# armBandShield.net
KiCad netlist of a schematic drawn in EAGLE
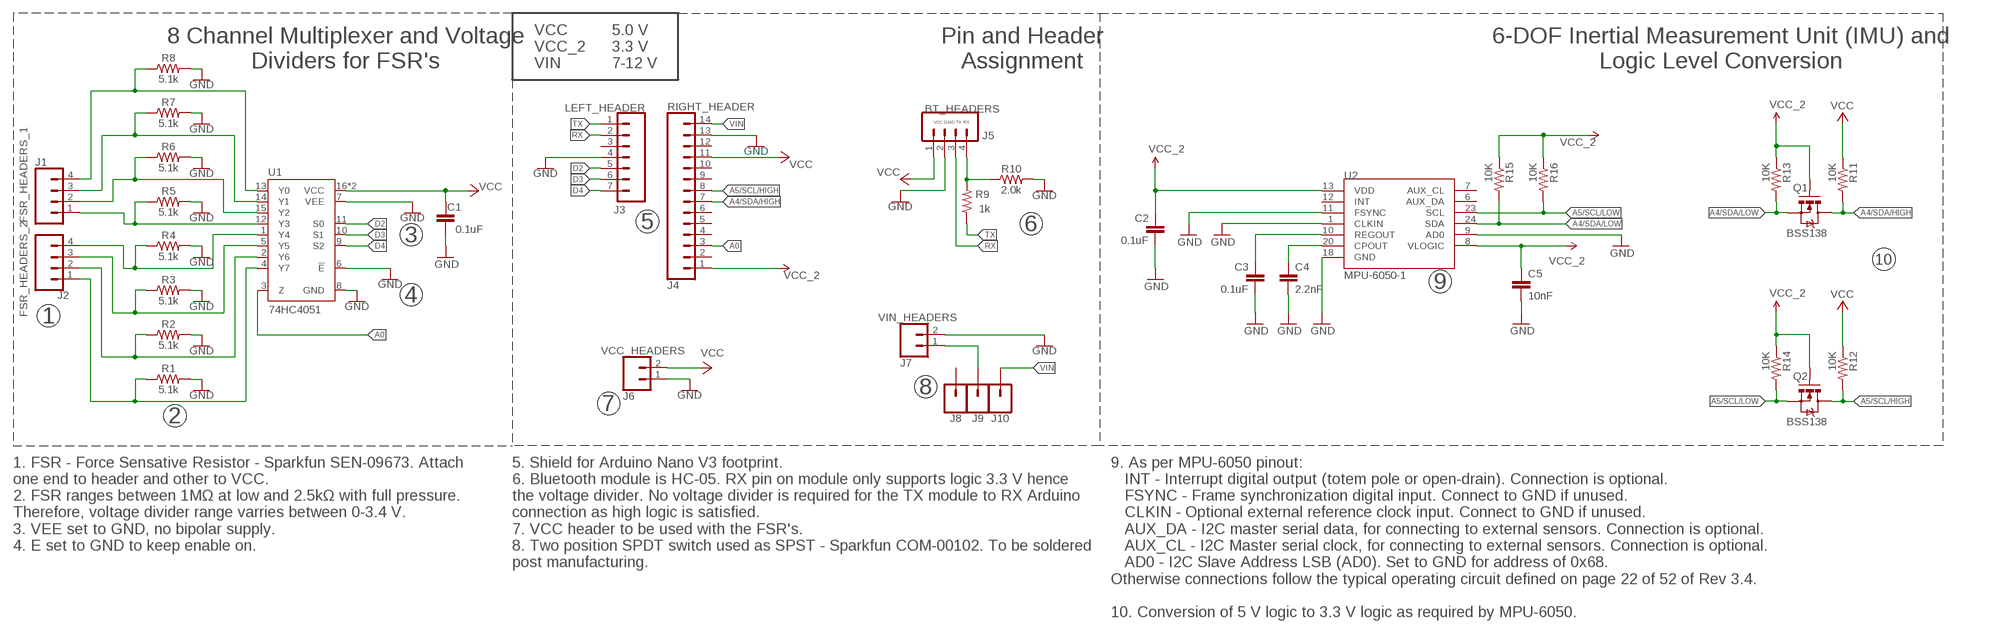
[diagram p0: schematic, sheet 1]

(export (version "E")
  (design (tool "Eeschema 10.0.6"))
  (components
    (comp (ref "74HC4051")
      (value "U1")
      (footprint "eagle-import:DHVQFN-16-2.5X3.5MM")
      (libsource (lib "eagle-import") (part "744051BQHC"))
    )
    (comp (ref "BT_HEADERS")
      (value "J5")
      (footprint "eagle-import:1X04")
      (libsource (lib "eagle-import") (part "CONN_04"))
    )
    (comp (ref "C1")
      (value "0.1uF")
      (footprint "eagle-import:0603-CAP")
      (libsource (lib "eagle-import") (part "0.1UF-25V(+80/-20%)(0603)"))
    )
    (comp (ref "C2")
      (value "0.1uF")
      (footprint "eagle-import:0603-CAP")
      (libsource (lib "eagle-import") (part "0.1UF-25V(+80/-20%)(0603)"))
    )
    (comp (ref "C3")
      (value "0.1uF")
      (footprint "eagle-import:0603-CAP")
      (libsource (lib "eagle-import") (part "0.1UF-25V(+80/-20%)(0603)"))
    )
    (comp (ref "C4")
      (value "2.2nF")
      (footprint "eagle-import:0603")
      (libsource (lib "eagle-import") (part "2.2NF/2200PF-0603-50V-10%"))
    )
    (comp (ref "C5")
      (value "10nF")
      (footprint "eagle-import:0603")
      (libsource (lib "eagle-import") (part "10NF-0603-50V-10%"))
    )
    (comp (ref "J1")
      (value "FSR_HEADERS_1")
      (footprint "eagle-import:1X04")
      (libsource (lib "eagle-import") (part "CONN_04"))
    )
    (comp (ref "J2")
      (value "FSR_HEADERS_2")
      (footprint "eagle-import:1X04")
      (libsource (lib "eagle-import") (part "CONN_04"))
    )
    (comp (ref "J8")
      (value "CONN_01")
      (footprint "eagle-import:1X01")
      (libsource (lib "eagle-import") (part "CONN_01"))
    )
    (comp (ref "J9")
      (value "CONN_01")
      (footprint "eagle-import:1X01")
      (libsource (lib "eagle-import") (part "CONN_01"))
    )
    (comp (ref "J10")
      (value "CONN_01")
      (footprint "eagle-import:1X01")
      (libsource (lib "eagle-import") (part "CONN_01"))
    )
    (comp (ref "LEFT_HEADER")
      (value "J3")
      (footprint "eagle-import:1X07")
      (libsource (lib "eagle-import") (part "CONN_07"))
    )
    (comp (ref "Q1")
      (value "BSS138")
      (footprint "eagle-import:SOT23-3")
      (libsource (lib "eagle-import") (part "MOSFET-NCHANNELSMD"))
    )
    (comp (ref "Q2")
      (value "BSS138")
      (footprint "eagle-import:SOT23-3")
      (libsource (lib "eagle-import") (part "MOSFET-NCHANNELSMD"))
    )
    (comp (ref "R1")
      (value "5.1k")
      (footprint "eagle-import:0603")
      (libsource (lib "eagle-import") (part "5.1KOHM5.1KOHM-0603-1/10W-1%"))
    )
    (comp (ref "R2")
      (value "5.1k")
      (footprint "eagle-import:0603")
      (libsource (lib "eagle-import") (part "5.1KOHM5.1KOHM-0603-1/10W-1%"))
    )
    (comp (ref "R3")
      (value "5.1k")
      (footprint "eagle-import:0603")
      (libsource (lib "eagle-import") (part "5.1KOHM5.1KOHM-0603-1/10W-1%"))
    )
    (comp (ref "R4")
      (value "5.1k")
      (footprint "eagle-import:0603")
      (libsource (lib "eagle-import") (part "5.1KOHM5.1KOHM-0603-1/10W-1%"))
    )
    (comp (ref "R5")
      (value "5.1k")
      (footprint "eagle-import:0603")
      (libsource (lib "eagle-import") (part "5.1KOHM5.1KOHM-0603-1/10W-1%"))
    )
    (comp (ref "R6")
      (value "5.1k")
      (footprint "eagle-import:0603")
      (libsource (lib "eagle-import") (part "5.1KOHM5.1KOHM-0603-1/10W-1%"))
    )
    (comp (ref "R7")
      (value "5.1k")
      (footprint "eagle-import:0603")
      (libsource (lib "eagle-import") (part "5.1KOHM5.1KOHM-0603-1/10W-1%"))
    )
    (comp (ref "R8")
      (value "5.1k")
      (footprint "eagle-import:0603")
      (libsource (lib "eagle-import") (part "5.1KOHM5.1KOHM-0603-1/10W-1%"))
    )
    (comp (ref "R9")
      (value "1k")
      (footprint "eagle-import:0603")
      (libsource (lib "eagle-import") (part "1KOHM-0603-1/10W-1%"))
    )
    (comp (ref "R10")
      (value "2.0k")
      (footprint "eagle-import:0603")
      (libsource (lib "eagle-import") (part "2.0KOHM-0603-1/10W-5%"))
    )
    (comp (ref "R11")
      (value "10K")
      (footprint "eagle-import:0603-RES")
      (libsource (lib "eagle-import") (part "RESISTOR0603-RES"))
    )
    (comp (ref "R12")
      (value "10K")
      (footprint "eagle-import:0603-RES")
      (libsource (lib "eagle-import") (part "RESISTOR0603-RES"))
    )
    (comp (ref "R13")
      (value "10K")
      (footprint "eagle-import:0603-RES")
      (libsource (lib "eagle-import") (part "RESISTOR0603-RES"))
    )
    (comp (ref "R14")
      (value "10K")
      (footprint "eagle-import:0603-RES")
      (libsource (lib "eagle-import") (part "RESISTOR0603-RES"))
    )
    (comp (ref "R15")
      (value "10K")
      (footprint "eagle-import:0603-RES")
      (libsource (lib "eagle-import") (part "10KOHM-1/10W-1%(0603)0603"))
    )
    (comp (ref "R16")
      (value "10K")
      (footprint "eagle-import:0603-RES")
      (libsource (lib "eagle-import") (part "10KOHM-1/10W-1%(0603)0603"))
    )
    (comp (ref "RIGHT_HEADER")
      (value "J4")
      (footprint "eagle-import:1X14")
      (libsource (lib "eagle-import") (part "CONN_14"))
    )
    (comp (ref "U2")
      (value "MPU-6050-1")
      (footprint "eagle-import:QFN-24-4MM2")
      (libsource (lib "eagle-import") (part "MPU-6050-1"))
    )
    (comp (ref "VCC_HEADERS")
      (value "J6")
      (footprint "eagle-import:1X02_LONGPADS")
      (libsource (lib "eagle-import") (part "CONN_02PTH3"))
    )
    (comp (ref "VIN_HEADERS")
      (value "J7")
      (footprint "eagle-import:1X02_LONGPADS")
      (libsource (lib "eagle-import") (part "CONN_02PTH3"))
    )
  )
  (nets
    (net (code "1") (name "A0") (class "Default")
      (node (ref "74HC4051") (pin "3") (pinfunction "Z_3") (pintype "bidirectional"))
      (node (ref "RIGHT_HEADER") (pin "3") (pinfunction "3_3") (pintype "passive"))
    )
    (net (code "2") (name "A4{slash}SDA{slash}HIGH") (class "Default")
      (node (ref "Q1") (pin "3") (pinfunction "D_3") (pintype "passive"))
      (node (ref "R11") (pin "2") (pinfunction "2_2") (pintype "passive"))
      (node (ref "RIGHT_HEADER") (pin "7") (pinfunction "7_7") (pintype "passive"))
    )
    (net (code "3") (name "A4{slash}SDA{slash}LOW") (class "Default")
      (node (ref "Q1") (pin "2") (pinfunction "S_2") (pintype "passive"))
      (node (ref "R13") (pin "2") (pinfunction "2_2") (pintype "passive"))
      (node (ref "R15") (pin "2") (pinfunction "2_2") (pintype "passive"))
      (node (ref "U2") (pin "24") (pinfunction "SDA_24") (pintype "bidirectional"))
    )
    (net (code "4") (name "A5{slash}SCL{slash}HIGH") (class "Default")
      (node (ref "Q2") (pin "3") (pinfunction "D_3") (pintype "passive"))
      (node (ref "R12") (pin "2") (pinfunction "2_2") (pintype "passive"))
      (node (ref "RIGHT_HEADER") (pin "8") (pinfunction "8_8") (pintype "passive"))
    )
    (net (code "5") (name "A5{slash}SCL{slash}LOW") (class "Default")
      (node (ref "Q2") (pin "2") (pinfunction "S_2") (pintype "passive"))
      (node (ref "R14") (pin "2") (pinfunction "2_2") (pintype "passive"))
      (node (ref "R16") (pin "2") (pinfunction "2_2") (pintype "passive"))
      (node (ref "U2") (pin "23") (pinfunction "SCL_23") (pintype "bidirectional"))
    )
    (net (code "6") (name "D2") (class "Default")
      (node (ref "74HC4051") (pin "11") (pinfunction "S0_11") (pintype "bidirectional"))
      (node (ref "LEFT_HEADER") (pin "5") (pinfunction "5_5") (pintype "passive"))
    )
    (net (code "7") (name "D3") (class "Default")
      (node (ref "74HC4051") (pin "10") (pinfunction "S1_10") (pintype "bidirectional"))
      (node (ref "LEFT_HEADER") (pin "6") (pinfunction "6_6") (pintype "passive"))
    )
    (net (code "8") (name "D4") (class "Default")
      (node (ref "74HC4051") (pin "9") (pinfunction "S2_9") (pintype "bidirectional"))
      (node (ref "LEFT_HEADER") (pin "7") (pinfunction "7_7") (pintype "passive"))
    )
    (net (code "9") (name "GND") (class "Default")
      (node (ref "74HC4051") (pin "6") (pinfunction "~{E}_6") (pintype "bidirectional"))
      (node (ref "74HC4051") (pin "7") (pinfunction "VEE_7") (pintype "bidirectional"))
      (node (ref "74HC4051") (pin "8") (pinfunction "GND_8") (pintype "bidirectional"))
      (node (ref "BT_HEADERS") (pin "2") (pinfunction "2_2") (pintype "passive"))
      (node (ref "C1") (pin "2") (pinfunction "2_2") (pintype "passive"))
      (node (ref "C2") (pin "2") (pinfunction "2_2") (pintype "passive"))
      (node (ref "C3") (pin "2") (pinfunction "2_2") (pintype "passive"))
      (node (ref "C4") (pin "2") (pinfunction "2_2") (pintype "passive"))
      (node (ref "C5") (pin "2") (pinfunction "2_2") (pintype "passive"))
      (node (ref "LEFT_HEADER") (pin "4") (pinfunction "4_4") (pintype "passive"))
      (node (ref "R1") (pin "2") (pinfunction "2_2") (pintype "passive"))
      (node (ref "R10") (pin "2") (pinfunction "2_2") (pintype "passive"))
      (node (ref "R2") (pin "2") (pinfunction "2_2") (pintype "passive"))
      (node (ref "R3") (pin "2") (pinfunction "2_2") (pintype "passive"))
      (node (ref "R4") (pin "2") (pinfunction "2_2") (pintype "passive"))
      (node (ref "R5") (pin "2") (pinfunction "2_2") (pintype "passive"))
      (node (ref "R6") (pin "2") (pinfunction "2_2") (pintype "passive"))
      (node (ref "R7") (pin "2") (pinfunction "2_2") (pintype "passive"))
      (node (ref "R8") (pin "2") (pinfunction "2_2") (pintype "passive"))
      (node (ref "RIGHT_HEADER") (pin "13") (pinfunction "13_13") (pintype "passive"))
      (node (ref "U2") (pin "1") (pinfunction "CLKIN_1") (pintype "bidirectional"))
      (node (ref "U2") (pin "11") (pinfunction "FSYNC_11") (pintype "bidirectional"))
      (node (ref "U2") (pin "18") (pinfunction "GND_18") (pintype "bidirectional"))
      (node (ref "U2") (pin "9") (pinfunction "AD0_9") (pintype "bidirectional"))
      (node (ref "VCC_HEADERS") (pin "1") (pinfunction "1_1") (pintype "passive"))
      (node (ref "VIN_HEADERS") (pin "2") (pinfunction "2_2") (pintype "passive"))
    )
    (net (code "10") (name "Net-(74HC4051-Y0)") (class "Default")
      (node (ref "74HC4051") (pin "13") (pinfunction "Y0_13") (pintype "bidirectional"))
      (node (ref "J1") (pin "4") (pinfunction "4_4") (pintype "passive"))
      (node (ref "R8") (pin "1") (pinfunction "1_1") (pintype "passive"))
    )
    (net (code "11") (name "Net-(74HC4051-Y1)") (class "Default")
      (node (ref "74HC4051") (pin "14") (pinfunction "Y1_14") (pintype "bidirectional"))
      (node (ref "J1") (pin "3") (pinfunction "3_3") (pintype "passive"))
      (node (ref "R7") (pin "1") (pinfunction "1_1") (pintype "passive"))
    )
    (net (code "12") (name "Net-(74HC4051-Y2)") (class "Default")
      (node (ref "74HC4051") (pin "15") (pinfunction "Y2_15") (pintype "bidirectional"))
      (node (ref "J1") (pin "2") (pinfunction "2_2") (pintype "passive"))
      (node (ref "R6") (pin "1") (pinfunction "1_1") (pintype "passive"))
    )
    (net (code "13") (name "Net-(74HC4051-Y3)") (class "Default")
      (node (ref "74HC4051") (pin "12") (pinfunction "Y3_12") (pintype "bidirectional"))
      (node (ref "J1") (pin "1") (pinfunction "1_1") (pintype "passive"))
      (node (ref "R5") (pin "1") (pinfunction "1_1") (pintype "passive"))
    )
    (net (code "14") (name "Net-(74HC4051-Y4)") (class "Default")
      (node (ref "74HC4051") (pin "1") (pinfunction "Y4_1") (pintype "bidirectional"))
      (node (ref "J2") (pin "4") (pinfunction "4_4") (pintype "passive"))
      (node (ref "R4") (pin "1") (pinfunction "1_1") (pintype "passive"))
    )
    (net (code "15") (name "Net-(74HC4051-Y5)") (class "Default")
      (node (ref "74HC4051") (pin "5") (pinfunction "Y5_5") (pintype "bidirectional"))
      (node (ref "J2") (pin "3") (pinfunction "3_3") (pintype "passive"))
      (node (ref "R3") (pin "1") (pinfunction "1_1") (pintype "passive"))
    )
    (net (code "16") (name "Net-(74HC4051-Y6)") (class "Default")
      (node (ref "74HC4051") (pin "2") (pinfunction "Y6_2") (pintype "bidirectional"))
      (node (ref "J2") (pin "2") (pinfunction "2_2") (pintype "passive"))
      (node (ref "R2") (pin "1") (pinfunction "1_1") (pintype "passive"))
    )
    (net (code "17") (name "Net-(74HC4051-Y7)") (class "Default")
      (node (ref "74HC4051") (pin "4") (pinfunction "Y7_4") (pintype "bidirectional"))
      (node (ref "J2") (pin "1") (pinfunction "1_1") (pintype "passive"))
      (node (ref "R1") (pin "1") (pinfunction "1_1") (pintype "passive"))
    )
    (net (code "18") (name "Net-(BT_HEADERS-Pad4)") (class "Default")
      (node (ref "BT_HEADERS") (pin "4") (pinfunction "4_4") (pintype "passive"))
      (node (ref "R10") (pin "1") (pinfunction "1_1") (pintype "passive"))
      (node (ref "R9") (pin "2") (pinfunction "2_2") (pintype "passive"))
    )
    (net (code "19") (name "Net-(J9-Pad1)") (class "Default")
      (node (ref "J9") (pin "1") (pinfunction "1_1") (pintype "passive"))
      (node (ref "VIN_HEADERS") (pin "1") (pinfunction "1_1") (pintype "passive"))
    )
    (net (code "20") (name "Net-(U2-CPOUT)") (class "Default")
      (node (ref "C4") (pin "1") (pinfunction "1_1") (pintype "passive"))
      (node (ref "U2") (pin "20") (pinfunction "CPOUT_20") (pintype "bidirectional"))
    )
    (net (code "21") (name "Net-(U2-REGOUT)") (class "Default")
      (node (ref "C3") (pin "1") (pinfunction "1_1") (pintype "passive"))
      (node (ref "U2") (pin "10") (pinfunction "REGOUT_10") (pintype "bidirectional"))
    )
    (net (code "22") (name "RX") (class "Default")
      (node (ref "BT_HEADERS") (pin "3") (pinfunction "3_3") (pintype "passive"))
      (node (ref "LEFT_HEADER") (pin "2") (pinfunction "2_2") (pintype "passive"))
    )
    (net (code "23") (name "TX") (class "Default")
      (node (ref "LEFT_HEADER") (pin "1") (pinfunction "1_1") (pintype "passive"))
      (node (ref "R9") (pin "1") (pinfunction "1_1") (pintype "passive"))
    )
    (net (code "24") (name "VCC") (class "Default")
      (node (ref "74HC4051") (pin "16") (pinfunction "VCC_16") (pintype "bidirectional"))
      (node (ref "74HC4051") (pin "EP") (pinfunction "VCC_EP") (pintype "bidirectional"))
      (node (ref "BT_HEADERS") (pin "1") (pinfunction "1_1") (pintype "passive"))
      (node (ref "C1") (pin "1") (pinfunction "1_1") (pintype "passive"))
      (node (ref "R11") (pin "1") (pinfunction "1_1") (pintype "passive"))
      (node (ref "R12") (pin "1") (pinfunction "1_1") (pintype "passive"))
      (node (ref "RIGHT_HEADER") (pin "11") (pinfunction "11_11") (pintype "passive"))
      (node (ref "VCC_HEADERS") (pin "2") (pinfunction "2_2") (pintype "passive"))
    )
    (net (code "25") (name "VCC_2") (class "Default")
      (node (ref "C2") (pin "1") (pinfunction "1_1") (pintype "passive"))
      (node (ref "C5") (pin "1") (pinfunction "1_1") (pintype "passive"))
      (node (ref "Q1") (pin "1") (pinfunction "G_1") (pintype "passive"))
      (node (ref "Q2") (pin "1") (pinfunction "G_1") (pintype "passive"))
      (node (ref "R13") (pin "1") (pinfunction "1_1") (pintype "passive"))
      (node (ref "R14") (pin "1") (pinfunction "1_1") (pintype "passive"))
      (node (ref "R15") (pin "1") (pinfunction "1_1") (pintype "passive"))
      (node (ref "R16") (pin "1") (pinfunction "1_1") (pintype "passive"))
      (node (ref "RIGHT_HEADER") (pin "1") (pinfunction "1_1") (pintype "passive"))
      (node (ref "U2") (pin "13") (pinfunction "VDD_13") (pintype "bidirectional"))
      (node (ref "U2") (pin "8") (pinfunction "VLOGIC_8") (pintype "bidirectional"))
    )
    (net (code "26") (name "VIN") (class "Default")
      (node (ref "J10") (pin "1") (pinfunction "1_1") (pintype "passive"))
      (node (ref "RIGHT_HEADER") (pin "14") (pinfunction "14_14") (pintype "passive"))
    )
    (net (code "27") (name "unconnected-(J8-Pad1)") (class "Default")
      (node (ref "J8") (pin "1") (pinfunction "1_1") (pintype "passive"))
    )
    (net (code "28") (name "unconnected-(LEFT_HEADER-Pad3)") (class "Default")
      (node (ref "LEFT_HEADER") (pin "3") (pinfunction "3_3") (pintype "passive"))
    )
    (net (code "29") (name "unconnected-(RIGHT_HEADER-Pad2)") (class "Default")
      (node (ref "RIGHT_HEADER") (pin "2") (pinfunction "2_2") (pintype "passive"))
    )
    (net (code "30") (name "unconnected-(RIGHT_HEADER-Pad4)") (class "Default")
      (node (ref "RIGHT_HEADER") (pin "4") (pinfunction "4_4") (pintype "passive"))
    )
    (net (code "31") (name "unconnected-(RIGHT_HEADER-Pad5)") (class "Default")
      (node (ref "RIGHT_HEADER") (pin "5") (pinfunction "5_5") (pintype "passive"))
    )
    (net (code "32") (name "unconnected-(RIGHT_HEADER-Pad6)") (class "Default")
      (node (ref "RIGHT_HEADER") (pin "6") (pinfunction "6_6") (pintype "passive"))
    )
    (net (code "33") (name "unconnected-(RIGHT_HEADER-Pad9)") (class "Default")
      (node (ref "RIGHT_HEADER") (pin "9") (pinfunction "9_9") (pintype "passive"))
    )
    (net (code "34") (name "unconnected-(RIGHT_HEADER-Pad10)") (class "Default")
      (node (ref "RIGHT_HEADER") (pin "10") (pinfunction "10_10") (pintype "passive"))
    )
    (net (code "35") (name "unconnected-(RIGHT_HEADER-Pad12)") (class "Default")
      (node (ref "RIGHT_HEADER") (pin "12") (pinfunction "12_12") (pintype "passive"))
    )
    (net (code "36") (name "unconnected-(U2-AUX_CL-Pad7)") (class "Default")
      (node (ref "U2") (pin "7") (pinfunction "AUX_CL_7") (pintype "bidirectional"))
    )
    (net (code "37") (name "unconnected-(U2-AUX_DA-Pad6)") (class "Default")
      (node (ref "U2") (pin "6") (pinfunction "AUX_DA_6") (pintype "bidirectional"))
    )
    (net (code "38") (name "unconnected-(U2-INT-Pad12)") (class "Default")
      (node (ref "U2") (pin "12") (pinfunction "INT_12") (pintype "bidirectional"))
    )
  )
)
